# SENSOR.net
KiCad netlist of a schematic drawn in Altium Designer
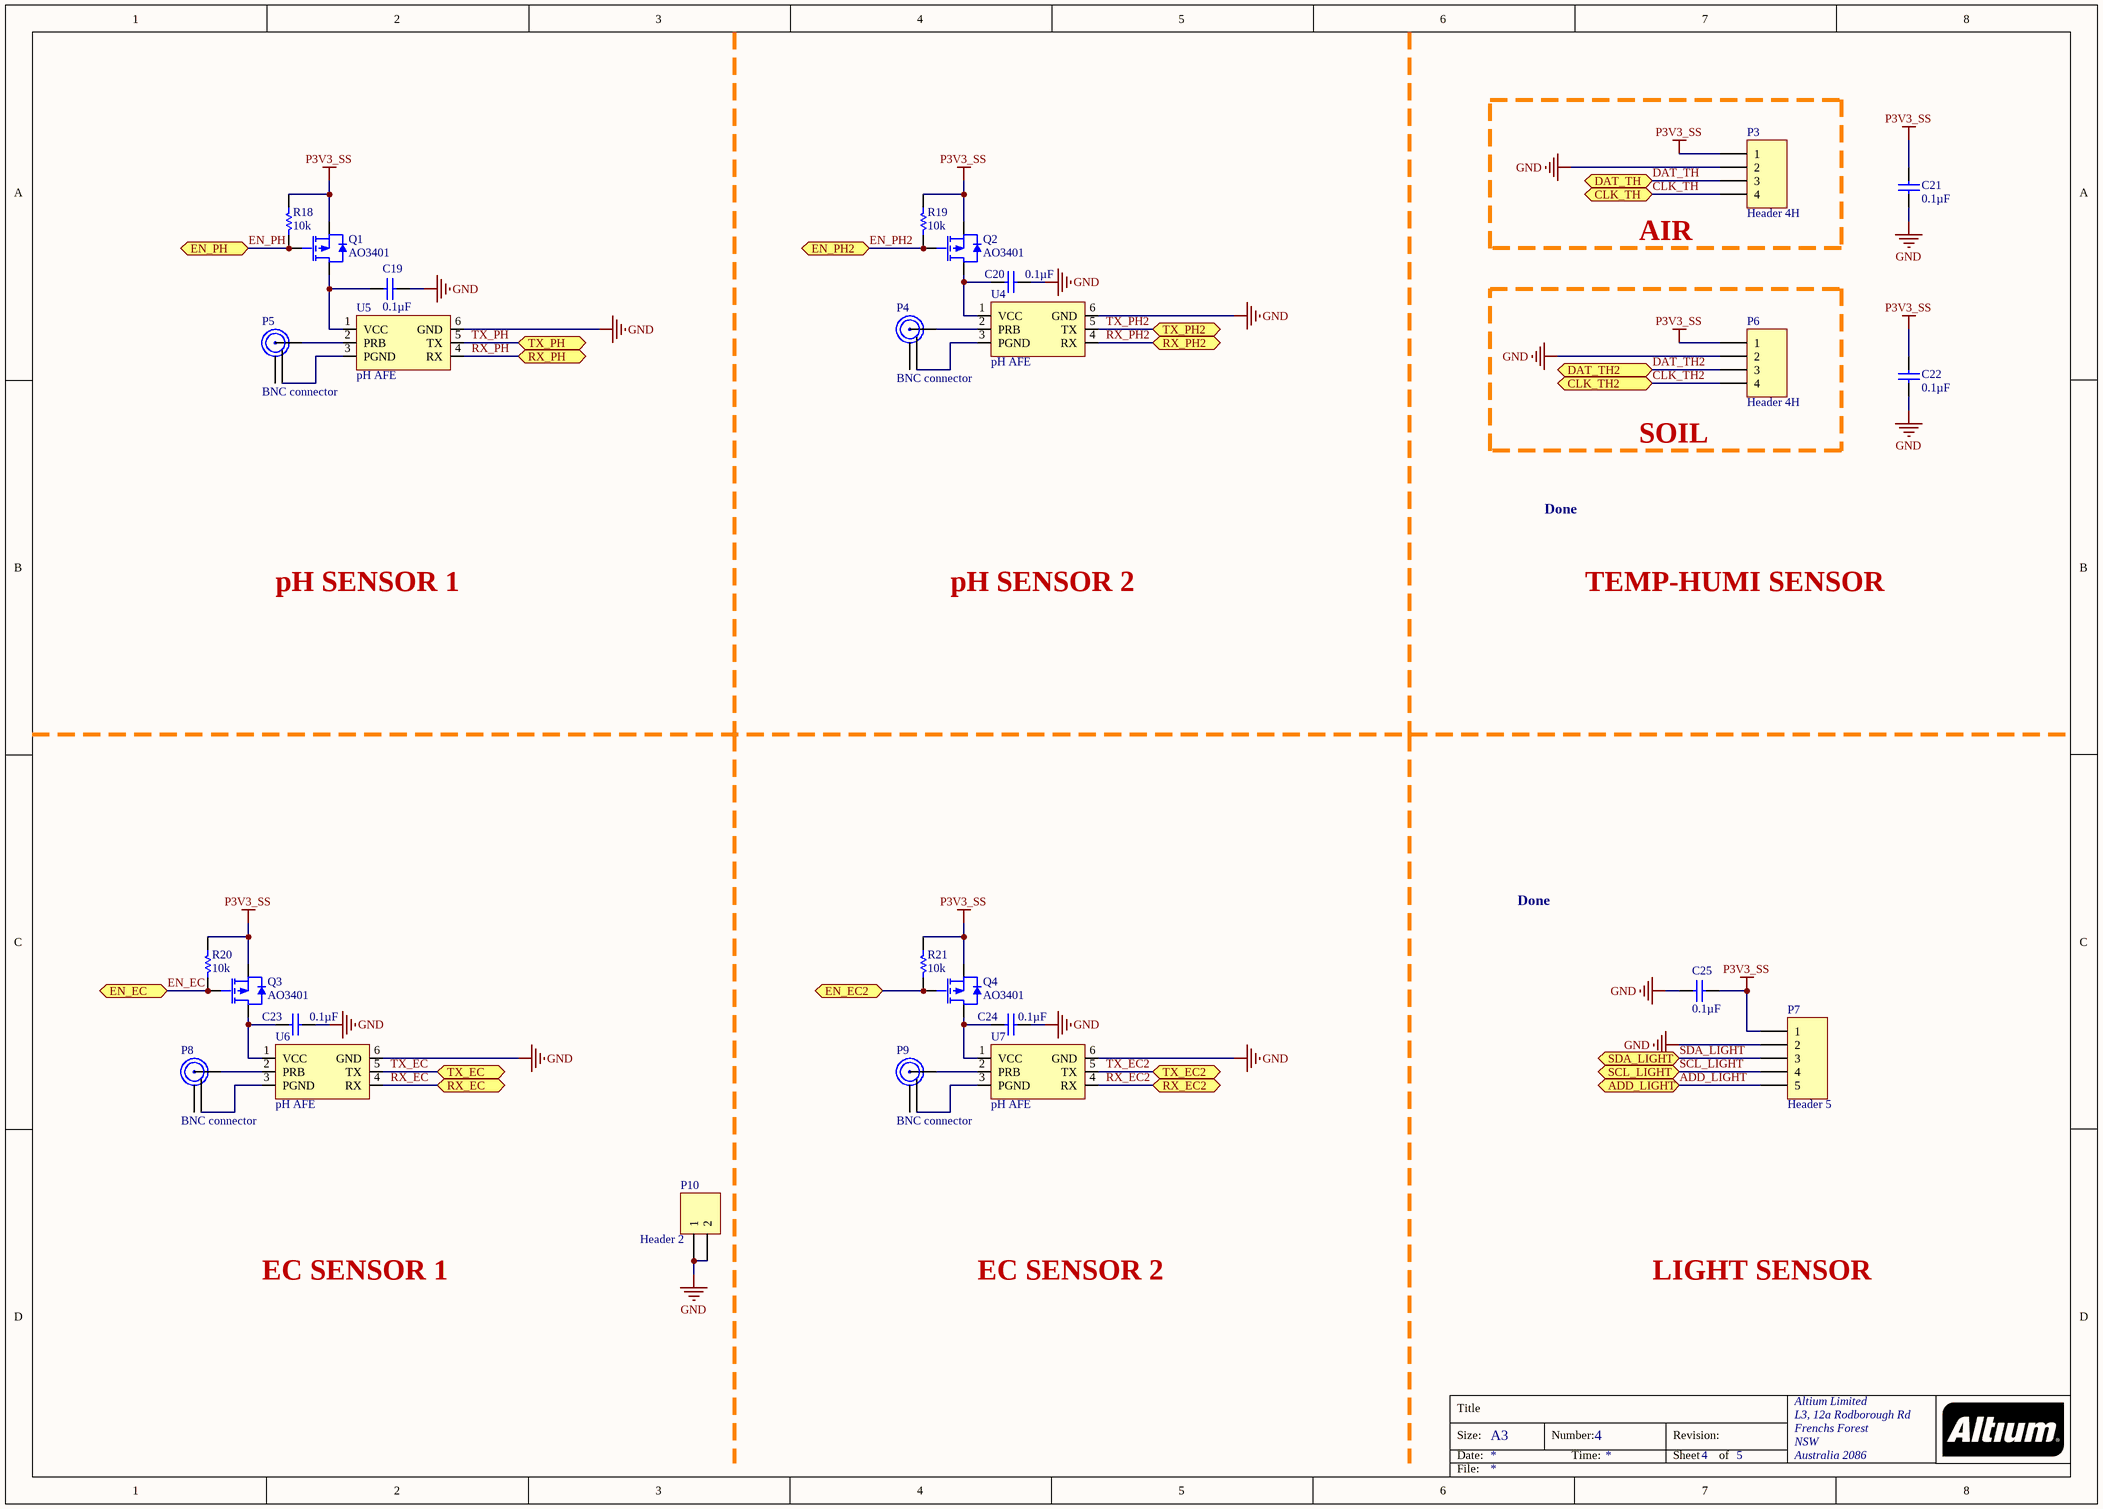
[diagram p0: SENSOR.SchDoc]

(export (version "E")
  (design (tool "Eeschema 10.0.6"))
  (components
    (comp (ref "C19")
      (value "0.1µF")
      (footprint "C0402M")
      (description "CAP CER 0.1UF 10V X7R 0402")
      (fields
        (field (name "MANUFACTURER") "Taiyo Yuden")
        (field (name "MANUFACTURER PART NUMBER") "LMK105B7104KVHF")
      )
      (libsource (lib "BinhLib") (part "CAP0.1u0402"))
    )
    (comp (ref "C20")
      (value "0.1µF")
      (footprint "C0402M")
      (description "CAP CER 0.1UF 10V X7R 0402")
      (fields
        (field (name "MANUFACTURER") "Taiyo Yuden")
        (field (name "MANUFACTURER PART NUMBER") "LMK105B7104KVHF")
      )
      (libsource (lib "BinhLib") (part "CAP0.1u0402"))
    )
    (comp (ref "C21")
      (value "0.1µF")
      (footprint "C0402M")
      (description "CAP CER 0.1UF 10V X7R 0402")
      (fields
        (field (name "MANUFACTURER") "Taiyo Yuden")
        (field (name "MANUFACTURER PART NUMBER") "LMK105B7104KVHF")
      )
      (libsource (lib "BinhLib") (part "CAP0.1u0402"))
    )
    (comp (ref "C22")
      (value "0.1µF")
      (footprint "C0402M")
      (description "CAP CER 0.1UF 10V X7R 0402")
      (fields
        (field (name "MANUFACTURER") "Taiyo Yuden")
        (field (name "MANUFACTURER PART NUMBER") "LMK105B7104KVHF")
      )
      (libsource (lib "BinhLib") (part "CAP0.1u0402"))
    )
    (comp (ref "C23")
      (value "0.1µF")
      (footprint "C0402M")
      (description "CAP CER 0.1UF 10V X7R 0402")
      (fields
        (field (name "MANUFACTURER") "Taiyo Yuden")
        (field (name "MANUFACTURER PART NUMBER") "LMK105B7104KVHF")
      )
      (libsource (lib "BinhLib") (part "CAP0.1u0402"))
    )
    (comp (ref "C24")
      (value "0.1µF")
      (footprint "C0402M")
      (description "CAP CER 0.1UF 10V X7R 0402")
      (fields
        (field (name "MANUFACTURER") "Taiyo Yuden")
        (field (name "MANUFACTURER PART NUMBER") "LMK105B7104KVHF")
      )
      (libsource (lib "BinhLib") (part "CAP0.1u0402"))
    )
    (comp (ref "C25")
      (value "0.1µF")
      (footprint "C0402M")
      (description "CAP CER 0.1UF 10V X7R 0402")
      (fields
        (field (name "MANUFACTURER") "Taiyo Yuden")
        (field (name "MANUFACTURER PART NUMBER") "LMK105B7104KVHF")
      )
      (libsource (lib "BinhLib") (part "CAP0.1u0402"))
    )
    (comp (ref "P3")
      (value "Header 4H")
      (footprint "TERMINAL4_5.08")
      (description "TERM BLOCK PLUG 4POS STR 5.08MM")
      (fields
        (field (name "MANUFACTURER") "Phoenix Contact")
        (field (name "MANUFACTURER PART NUMBER") "1758377")
        (field (name "PUBLISHER") "Altium Limited")
      )
      (libsource (lib "BinhLib") (part "Header 4H"))
    )
    (comp (ref "P4")
      (value "BNC connector")
      (footprint "BNC")
      (libsource (lib "BinhLib") (part "BNC connector"))
    )
    (comp (ref "P5")
      (value "BNC connector")
      (footprint "BNC")
      (libsource (lib "BinhLib") (part "BNC connector"))
    )
    (comp (ref "P6")
      (value "Header 4H")
      (footprint "TERMINAL4_5.08")
      (description "TERM BLOCK PLUG 4POS STR 5.08MM")
      (fields
        (field (name "MANUFACTURER") "Phoenix Contact")
        (field (name "MANUFACTURER PART NUMBER") "1758377")
        (field (name "PUBLISHER") "Altium Limited")
      )
      (libsource (lib "BinhLib") (part "Header 4H"))
    )
    (comp (ref "P7")
      (value "Header 5")
      (footprint "TERMINAL5_5.08")
      (description "TERM BLOCK PLUG 5POS STR 5.08MM")
      (fields
        (field (name "MANUFACTURER") "Phoenix Contact")
        (field (name "MANUFACTURER PART NUMBER") "1757048")
        (field (name "PUBLISHER") "Altium Limited")
      )
      (libsource (lib "BinhLib") (part "Header 5"))
    )
    (comp (ref "P8")
      (value "BNC connector")
      (footprint "BNC")
      (libsource (lib "BinhLib") (part "BNC connector"))
    )
    (comp (ref "P9")
      (value "BNC connector")
      (footprint "BNC")
      (libsource (lib "BinhLib") (part "BNC connector"))
    )
    (comp (ref "P10")
      (value "Header 2")
      (footprint "HED2T")
      (description "Header, 2-Pin")
      (fields (field (name "PUBLISHER") "Altium Limited"))
      (libsource (lib "BinhLib") (part "Header 2"))
    )
    (comp (ref "Q1")
      (value "AO3401")
      (footprint "SOT23-3N")
      (description "P-Channel MOSFET")
      (libsource (lib "BinhLib") (part "MOSFET-P1"))
    )
    (comp (ref "Q2")
      (value "AO3401")
      (footprint "SOT23-3N")
      (description "P-Channel MOSFET")
      (libsource (lib "BinhLib") (part "MOSFET-P1"))
    )
    (comp (ref "Q3")
      (value "AO3401")
      (footprint "SOT23-3N")
      (description "P-Channel MOSFET")
      (libsource (lib "BinhLib") (part "MOSFET-P1"))
    )
    (comp (ref "Q4")
      (value "AO3401")
      (footprint "SOT23-3N")
      (description "P-Channel MOSFET")
      (libsource (lib "BinhLib") (part "MOSFET-P1"))
    )
    (comp (ref "R18")
      (value "10k")
      (footprint "R0603M")
      (description "RES SMD 10K OHM 1% 1/10W 0603")
      (fields
        (field (name "MANUFACTURER") "Panasonic Electronic Components")
        (field (name "MANUFACTURER PART NUMBER") "ERJ-3EKF1002V")
      )
      (libsource (lib "BinhLib") (part "RES10k0603"))
    )
    (comp (ref "R19")
      (value "10k")
      (footprint "R0603M")
      (description "RES SMD 10K OHM 1% 1/10W 0603")
      (fields
        (field (name "MANUFACTURER") "Panasonic Electronic Components")
        (field (name "MANUFACTURER PART NUMBER") "ERJ-3EKF1002V")
      )
      (libsource (lib "BinhLib") (part "RES10k0603"))
    )
    (comp (ref "R20")
      (value "10k")
      (footprint "R0603M")
      (description "RES SMD 10K OHM 1% 1/10W 0603")
      (fields
        (field (name "MANUFACTURER") "Panasonic Electronic Components")
        (field (name "MANUFACTURER PART NUMBER") "ERJ-3EKF1002V")
      )
      (libsource (lib "BinhLib") (part "RES10k0603"))
    )
    (comp (ref "R21")
      (value "10k")
      (footprint "R0603M")
      (description "RES SMD 10K OHM 1% 1/10W 0603")
      (fields
        (field (name "MANUFACTURER") "Panasonic Electronic Components")
        (field (name "MANUFACTURER PART NUMBER") "ERJ-3EKF1002V")
      )
      (libsource (lib "BinhLib") (part "RES10k0603"))
    )
    (comp (ref "U4") (value "pH AFE") (footprint "pH AFE") (libsource (lib "SensorNode") (part "pH AFE")))
    (comp (ref "U5") (value "pH AFE") (footprint "pH AFE") (libsource (lib "SensorNode") (part "pH AFE")))
    (comp (ref "U6") (value "pH AFE") (footprint "pH AFE") (libsource (lib "SensorNode") (part "pH AFE")))
    (comp (ref "U7") (value "pH AFE") (footprint "pH AFE") (libsource (lib "SensorNode") (part "pH AFE")))
  )
  (nets
    (net (code "1") (name "/ADD_LIGHT") (class "Default")
      (node (ref "P7") (pin "5") (pinfunction "5_5") (pintype "passive"))
    )
    (net (code "2") (name "/CLK_TH") (class "Default")
      (node (ref "P3") (pin "4") (pinfunction "4_4") (pintype "passive"))
    )
    (net (code "3") (name "/CLK_TH2") (class "Default")
      (node (ref "P6") (pin "4") (pinfunction "4_4") (pintype "passive"))
    )
    (net (code "4") (name "/DAT_TH") (class "Default")
      (node (ref "P3") (pin "3") (pinfunction "3_3") (pintype "passive"))
    )
    (net (code "5") (name "/DAT_TH2") (class "Default")
      (node (ref "P6") (pin "3") (pinfunction "3_3") (pintype "passive"))
    )
    (net (code "6") (name "/EN_EC") (class "Default")
      (node (ref "Q3") (pin "1") (pinfunction "G_1") (pintype "passive"))
      (node (ref "R20") (pin "1") (pinfunction "1_1") (pintype "passive"))
    )
    (net (code "7") (name "/EN_EC2") (class "Default")
      (node (ref "Q4") (pin "1") (pinfunction "G_1") (pintype "passive"))
      (node (ref "R21") (pin "1") (pinfunction "1_1") (pintype "passive"))
    )
    (net (code "8") (name "/EN_PH") (class "Default")
      (node (ref "Q1") (pin "1") (pinfunction "G_1") (pintype "passive"))
      (node (ref "R18") (pin "1") (pinfunction "1_1") (pintype "passive"))
    )
    (net (code "9") (name "/EN_PH2") (class "Default")
      (node (ref "Q2") (pin "1") (pinfunction "G_1") (pintype "passive"))
      (node (ref "R19") (pin "1") (pinfunction "1_1") (pintype "passive"))
    )
    (net (code "10") (name "/RX_EC") (class "Default")
      (node (ref "U6") (pin "4") (pinfunction "RX_4") (pintype "passive"))
    )
    (net (code "11") (name "/RX_EC2") (class "Default")
      (node (ref "U7") (pin "4") (pinfunction "RX_4") (pintype "passive"))
    )
    (net (code "12") (name "/RX_PH") (class "Default")
      (node (ref "U5") (pin "4") (pinfunction "RX_4") (pintype "passive"))
    )
    (net (code "13") (name "/RX_PH2") (class "Default")
      (node (ref "U4") (pin "4") (pinfunction "RX_4") (pintype "passive"))
    )
    (net (code "14") (name "/SCL_LIGHT") (class "Default")
      (node (ref "P7") (pin "4") (pinfunction "4_4") (pintype "passive"))
    )
    (net (code "15") (name "/SDA_LIGHT") (class "Default")
      (node (ref "P7") (pin "3") (pinfunction "3_3") (pintype "passive"))
    )
    (net (code "16") (name "/TX_EC") (class "Default")
      (node (ref "U6") (pin "5") (pinfunction "TX_5") (pintype "passive"))
    )
    (net (code "17") (name "/TX_EC2") (class "Default")
      (node (ref "U7") (pin "5") (pinfunction "TX_5") (pintype "passive"))
    )
    (net (code "18") (name "/TX_PH") (class "Default")
      (node (ref "U5") (pin "5") (pinfunction "TX_5") (pintype "passive"))
    )
    (net (code "19") (name "/TX_PH2") (class "Default")
      (node (ref "U4") (pin "5") (pinfunction "TX_5") (pintype "passive"))
    )
    (net (code "20") (name "GND") (class "Default")
      (node (ref "C19") (pin "1") (pintype "passive"))
      (node (ref "C20") (pin "1") (pintype "passive"))
      (node (ref "C21") (pin "1") (pintype "passive"))
      (node (ref "C22") (pin "1") (pintype "passive"))
      (node (ref "C23") (pin "1") (pintype "passive"))
      (node (ref "C24") (pin "1") (pintype "passive"))
      (node (ref "C25") (pin "1") (pintype "passive"))
      (node (ref "P10") (pin "1") (pinfunction "1_1") (pintype "passive"))
      (node (ref "P10") (pin "2") (pinfunction "2_2") (pintype "passive"))
      (node (ref "P3") (pin "2") (pinfunction "2_2") (pintype "passive"))
      (node (ref "P6") (pin "2") (pinfunction "2_2") (pintype "passive"))
      (node (ref "P7") (pin "2") (pinfunction "2_2") (pintype "passive"))
      (node (ref "U4") (pin "6") (pinfunction "GND_6") (pintype "passive"))
      (node (ref "U5") (pin "6") (pinfunction "GND_6") (pintype "passive"))
      (node (ref "U6") (pin "6") (pinfunction "GND_6") (pintype "passive"))
      (node (ref "U7") (pin "6") (pinfunction "GND_6") (pintype "passive"))
    )
    (net (code "21") (name "Net-(Q1-D)") (class "Default")
      (node (ref "C19") (pin "2") (pintype "passive"))
      (node (ref "Q1") (pin "3") (pinfunction "D_3") (pintype "passive"))
      (node (ref "U5") (pin "1") (pinfunction "VCC_1") (pintype "passive"))
    )
    (net (code "22") (name "Net-(Q2-D)") (class "Default")
      (node (ref "C20") (pin "2") (pintype "passive"))
      (node (ref "Q2") (pin "3") (pinfunction "D_3") (pintype "passive"))
      (node (ref "U4") (pin "1") (pinfunction "VCC_1") (pintype "passive"))
    )
    (net (code "23") (name "Net-(Q3-D)") (class "Default")
      (node (ref "C23") (pin "2") (pintype "passive"))
      (node (ref "Q3") (pin "3") (pinfunction "D_3") (pintype "passive"))
      (node (ref "U6") (pin "1") (pinfunction "VCC_1") (pintype "passive"))
    )
    (net (code "24") (name "Net-(Q4-D)") (class "Default")
      (node (ref "C24") (pin "2") (pintype "passive"))
      (node (ref "Q4") (pin "3") (pinfunction "D_3") (pintype "passive"))
      (node (ref "U7") (pin "1") (pinfunction "VCC_1") (pintype "passive"))
    )
    (net (code "25") (name "Net-(U4-PGND)") (class "Default")
      (node (ref "P4") (pin "2") (pintype "passive"))
      (node (ref "U4") (pin "3") (pinfunction "PGND_3") (pintype "passive"))
    )
    (net (code "26") (name "Net-(U4-PRB)") (class "Default")
      (node (ref "P4") (pin "1") (pintype "passive"))
      (node (ref "U4") (pin "2") (pinfunction "PRB_2") (pintype "passive"))
    )
    (net (code "27") (name "Net-(U5-PGND)") (class "Default")
      (node (ref "P5") (pin "2") (pintype "passive"))
      (node (ref "U5") (pin "3") (pinfunction "PGND_3") (pintype "passive"))
    )
    (net (code "28") (name "Net-(U5-PRB)") (class "Default")
      (node (ref "P5") (pin "1") (pintype "passive"))
      (node (ref "U5") (pin "2") (pinfunction "PRB_2") (pintype "passive"))
    )
    (net (code "29") (name "Net-(U6-PGND)") (class "Default")
      (node (ref "P8") (pin "2") (pintype "passive"))
      (node (ref "U6") (pin "3") (pinfunction "PGND_3") (pintype "passive"))
    )
    (net (code "30") (name "Net-(U6-PRB)") (class "Default")
      (node (ref "P8") (pin "1") (pintype "passive"))
      (node (ref "U6") (pin "2") (pinfunction "PRB_2") (pintype "passive"))
    )
    (net (code "31") (name "Net-(U7-PGND)") (class "Default")
      (node (ref "P9") (pin "2") (pintype "passive"))
      (node (ref "U7") (pin "3") (pinfunction "PGND_3") (pintype "passive"))
    )
    (net (code "32") (name "Net-(U7-PRB)") (class "Default")
      (node (ref "P9") (pin "1") (pintype "passive"))
      (node (ref "U7") (pin "2") (pinfunction "PRB_2") (pintype "passive"))
    )
    (net (code "33") (name "P3V3_SS") (class "Default")
      (node (ref "C21") (pin "2") (pintype "passive"))
      (node (ref "C22") (pin "2") (pintype "passive"))
      (node (ref "C25") (pin "2") (pintype "passive"))
      (node (ref "P3") (pin "1") (pinfunction "1_1") (pintype "passive"))
      (node (ref "P6") (pin "1") (pinfunction "1_1") (pintype "passive"))
      (node (ref "P7") (pin "1") (pinfunction "1_1") (pintype "passive"))
      (node (ref "Q1") (pin "2") (pinfunction "S_2") (pintype "passive"))
      (node (ref "Q2") (pin "2") (pinfunction "S_2") (pintype "passive"))
      (node (ref "Q3") (pin "2") (pinfunction "S_2") (pintype "passive"))
      (node (ref "Q4") (pin "2") (pinfunction "S_2") (pintype "passive"))
      (node (ref "R18") (pin "2") (pinfunction "2_2") (pintype "passive"))
      (node (ref "R19") (pin "2") (pinfunction "2_2") (pintype "passive"))
      (node (ref "R20") (pin "2") (pinfunction "2_2") (pintype "passive"))
      (node (ref "R21") (pin "2") (pinfunction "2_2") (pintype "passive"))
    )
    (net (code "34") (name "unconnected-(P4-Pad3)") (class "Default")
      (node (ref "P4") (pin "3") (pintype "passive"))
    )
    (net (code "35") (name "unconnected-(P5-Pad3)") (class "Default")
      (node (ref "P5") (pin "3") (pintype "passive"))
    )
    (net (code "36") (name "unconnected-(P8-Pad3)") (class "Default")
      (node (ref "P8") (pin "3") (pintype "passive"))
    )
    (net (code "37") (name "unconnected-(P9-Pad3)") (class "Default")
      (node (ref "P9") (pin "3") (pintype "passive"))
    )
  )
)
